# PHOTODIODE_CONT.net
KiCad netlist of a schematic drawn in Altium Designer
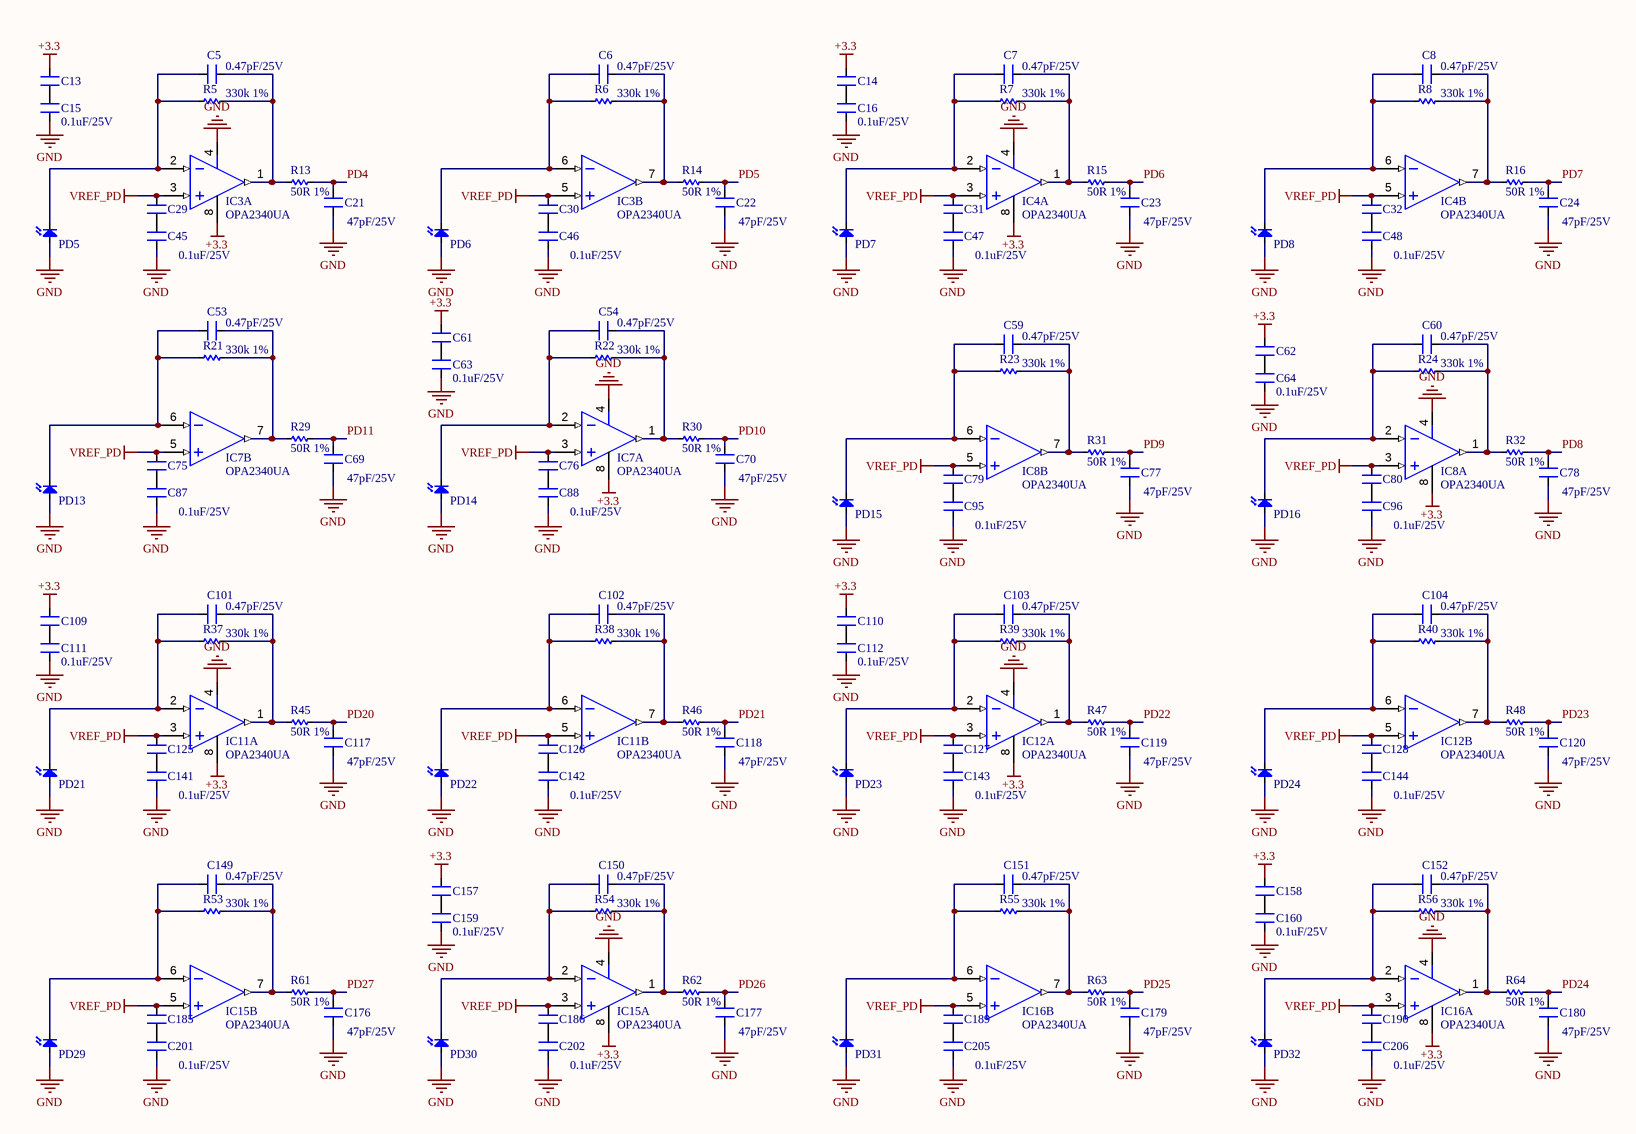
[diagram p0: PHOTODIODE (CONT).SchDoc]

(export (version "E")
  (design (tool "Eeschema 10.0.6"))
  (components
    (comp (ref "C5")
      (value "0.47pF/25V")
      (footprint "SM-0603")
      (description "0603")
      (libsource (lib "Capacitors") (part "CM"))
    )
    (comp (ref "C6")
      (value "0.47pF/25V")
      (footprint "SM-0603")
      (description "0603")
      (libsource (lib "Capacitors") (part "CM"))
    )
    (comp (ref "C7")
      (value "0.47pF/25V")
      (footprint "SM-0603")
      (description "0603")
      (libsource (lib "Capacitors") (part "CM"))
    )
    (comp (ref "C8")
      (value "0.47pF/25V")
      (footprint "SM-0603")
      (description "0603")
      (libsource (lib "Capacitors") (part "CM"))
    )
    (comp (ref "C13")
      (value "0.1uF/25V")
      (footprint "SM-0603")
      (description "0603")
      (libsource (lib "Capacitors") (part "CM"))
    )
    (comp (ref "C14")
      (value "0.1uF/25V")
      (footprint "SM-0603")
      (description "0603")
      (libsource (lib "Capacitors") (part "CM"))
    )
    (comp (ref "C15")
      (value "0.1uF/25V")
      (footprint "SM-0603")
      (description "0603")
      (libsource (lib "Capacitors") (part "CM"))
    )
    (comp (ref "C16")
      (value "0.1uF/25V")
      (footprint "SM-0603")
      (description "0603")
      (libsource (lib "Capacitors") (part "CM"))
    )
    (comp (ref "C21")
      (value "47pF/25V")
      (footprint "SM-0603")
      (description "0603")
      (libsource (lib "Capacitors") (part "CM"))
    )
    (comp (ref "C22")
      (value "47pF/25V")
      (footprint "SM-0603")
      (description "0603")
      (libsource (lib "Capacitors") (part "CM"))
    )
    (comp (ref "C23")
      (value "47pF/25V")
      (footprint "SM-0603")
      (description "0603")
      (libsource (lib "Capacitors") (part "CM"))
    )
    (comp (ref "C24")
      (value "47pF/25V")
      (footprint "SM-0603")
      (description "0603")
      (libsource (lib "Capacitors") (part "CM"))
    )
    (comp (ref "C29")
      (value "0.1uF/25V")
      (footprint "SM-0603")
      (description "0603")
      (libsource (lib "Capacitors") (part "CM"))
    )
    (comp (ref "C30")
      (value "0.1uF/25V")
      (footprint "SM-0603")
      (description "0603")
      (libsource (lib "Capacitors") (part "CM"))
    )
    (comp (ref "C31")
      (value "0.1uF/25V")
      (footprint "SM-0603")
      (description "0603")
      (libsource (lib "Capacitors") (part "CM"))
    )
    (comp (ref "C32")
      (value "0.1uF/25V")
      (footprint "SM-0603")
      (description "0603")
      (libsource (lib "Capacitors") (part "CM"))
    )
    (comp (ref "C45")
      (value "0.1uF/25V")
      (footprint "SM-0603")
      (description "0603")
      (libsource (lib "Capacitors") (part "CM"))
    )
    (comp (ref "C46")
      (value "0.1uF/25V")
      (footprint "SM-0603")
      (description "0603")
      (libsource (lib "Capacitors") (part "CM"))
    )
    (comp (ref "C47")
      (value "0.1uF/25V")
      (footprint "SM-0603")
      (description "0603")
      (libsource (lib "Capacitors") (part "CM"))
    )
    (comp (ref "C48")
      (value "0.1uF/25V")
      (footprint "SM-0603")
      (description "0603")
      (libsource (lib "Capacitors") (part "CM"))
    )
    (comp (ref "C53")
      (value "0.47pF/25V")
      (footprint "SM-0603")
      (description "0603")
      (libsource (lib "Capacitors") (part "CM"))
    )
    (comp (ref "C54")
      (value "0.47pF/25V")
      (footprint "SM-0603")
      (description "0603")
      (libsource (lib "Capacitors") (part "CM"))
    )
    (comp (ref "C59")
      (value "0.47pF/25V")
      (footprint "SM-0603")
      (description "0603")
      (libsource (lib "Capacitors") (part "CM"))
    )
    (comp (ref "C60")
      (value "0.47pF/25V")
      (footprint "SM-0603")
      (description "0603")
      (libsource (lib "Capacitors") (part "CM"))
    )
    (comp (ref "C61")
      (value "0.1uF/25V")
      (footprint "SM-0603")
      (description "0603")
      (libsource (lib "Capacitors") (part "CM"))
    )
    (comp (ref "C62")
      (value "0.1uF/25V")
      (footprint "SM-0603")
      (description "0603")
      (libsource (lib "Capacitors") (part "CM"))
    )
    (comp (ref "C63")
      (value "0.1uF/25V")
      (footprint "SM-0603")
      (description "0603")
      (libsource (lib "Capacitors") (part "CM"))
    )
    (comp (ref "C64")
      (value "0.1uF/25V")
      (footprint "SM-0603")
      (description "0603")
      (libsource (lib "Capacitors") (part "CM"))
    )
    (comp (ref "C69")
      (value "47pF/25V")
      (footprint "SM-0603")
      (description "0603")
      (libsource (lib "Capacitors") (part "CM"))
    )
    (comp (ref "C70")
      (value "47pF/25V")
      (footprint "SM-0603")
      (description "0603")
      (libsource (lib "Capacitors") (part "CM"))
    )
    (comp (ref "C75")
      (value "0.1uF/25V")
      (footprint "SM-0603")
      (description "0603")
      (libsource (lib "Capacitors") (part "CM"))
    )
    (comp (ref "C76")
      (value "0.1uF/25V")
      (footprint "SM-0603")
      (description "0603")
      (libsource (lib "Capacitors") (part "CM"))
    )
    (comp (ref "C77")
      (value "47pF/25V")
      (footprint "SM-0603")
      (description "0603")
      (libsource (lib "Capacitors") (part "CM"))
    )
    (comp (ref "C78")
      (value "47pF/25V")
      (footprint "SM-0603")
      (description "0603")
      (libsource (lib "Capacitors") (part "CM"))
    )
    (comp (ref "C79")
      (value "0.1uF/25V")
      (footprint "SM-0603")
      (description "0603")
      (libsource (lib "Capacitors") (part "CM"))
    )
    (comp (ref "C80")
      (value "0.1uF/25V")
      (footprint "SM-0603")
      (description "0603")
      (libsource (lib "Capacitors") (part "CM"))
    )
    (comp (ref "C87")
      (value "0.1uF/25V")
      (footprint "SM-0603")
      (description "0603")
      (libsource (lib "Capacitors") (part "CM"))
    )
    (comp (ref "C88")
      (value "0.1uF/25V")
      (footprint "SM-0603")
      (description "0603")
      (libsource (lib "Capacitors") (part "CM"))
    )
    (comp (ref "C95")
      (value "0.1uF/25V")
      (footprint "SM-0603")
      (description "0603")
      (libsource (lib "Capacitors") (part "CM"))
    )
    (comp (ref "C96")
      (value "0.1uF/25V")
      (footprint "SM-0603")
      (description "0603")
      (libsource (lib "Capacitors") (part "CM"))
    )
    (comp (ref "C101")
      (value "0.47pF/25V")
      (footprint "SM-0603")
      (description "0603")
      (libsource (lib "Capacitors") (part "CM"))
    )
    (comp (ref "C102")
      (value "0.47pF/25V")
      (footprint "SM-0603")
      (description "0603")
      (libsource (lib "Capacitors") (part "CM"))
    )
    (comp (ref "C103")
      (value "0.47pF/25V")
      (footprint "SM-0603")
      (description "0603")
      (libsource (lib "Capacitors") (part "CM"))
    )
    (comp (ref "C104")
      (value "0.47pF/25V")
      (footprint "SM-0603")
      (description "0603")
      (libsource (lib "Capacitors") (part "CM"))
    )
    (comp (ref "C109")
      (value "0.1uF/25V")
      (footprint "SM-0603")
      (description "0603")
      (libsource (lib "Capacitors") (part "CM"))
    )
    (comp (ref "C110")
      (value "0.1uF/25V")
      (footprint "SM-0603")
      (description "0603")
      (libsource (lib "Capacitors") (part "CM"))
    )
    (comp (ref "C111")
      (value "0.1uF/25V")
      (footprint "SM-0603")
      (description "0603")
      (libsource (lib "Capacitors") (part "CM"))
    )
    (comp (ref "C112")
      (value "0.1uF/25V")
      (footprint "SM-0603")
      (description "0603")
      (libsource (lib "Capacitors") (part "CM"))
    )
    (comp (ref "C117")
      (value "47pF/25V")
      (footprint "SM-0603")
      (description "0603")
      (libsource (lib "Capacitors") (part "CM"))
    )
    (comp (ref "C118")
      (value "47pF/25V")
      (footprint "SM-0603")
      (description "0603")
      (libsource (lib "Capacitors") (part "CM"))
    )
    (comp (ref "C119")
      (value "47pF/25V")
      (footprint "SM-0603")
      (description "0603")
      (libsource (lib "Capacitors") (part "CM"))
    )
    (comp (ref "C120")
      (value "47pF/25V")
      (footprint "SM-0603")
      (description "0603")
      (libsource (lib "Capacitors") (part "CM"))
    )
    (comp (ref "C125")
      (value "0.1uF/25V")
      (footprint "SM-0603")
      (description "0603")
      (libsource (lib "Capacitors") (part "CM"))
    )
    (comp (ref "C126")
      (value "0.1uF/25V")
      (footprint "SM-0603")
      (description "0603")
      (libsource (lib "Capacitors") (part "CM"))
    )
    (comp (ref "C127")
      (value "0.1uF/25V")
      (footprint "SM-0603")
      (description "0603")
      (libsource (lib "Capacitors") (part "CM"))
    )
    (comp (ref "C128")
      (value "0.1uF/25V")
      (footprint "SM-0603")
      (description "0603")
      (libsource (lib "Capacitors") (part "CM"))
    )
    (comp (ref "C141")
      (value "0.1uF/25V")
      (footprint "SM-0603")
      (description "0603")
      (libsource (lib "Capacitors") (part "CM"))
    )
    (comp (ref "C142")
      (value "0.1uF/25V")
      (footprint "SM-0603")
      (description "0603")
      (libsource (lib "Capacitors") (part "CM"))
    )
    (comp (ref "C143")
      (value "0.1uF/25V")
      (footprint "SM-0603")
      (description "0603")
      (libsource (lib "Capacitors") (part "CM"))
    )
    (comp (ref "C144")
      (value "0.1uF/25V")
      (footprint "SM-0603")
      (description "0603")
      (libsource (lib "Capacitors") (part "CM"))
    )
    (comp (ref "C149")
      (value "0.47pF/25V")
      (footprint "SM-0603")
      (description "0603")
      (libsource (lib "Capacitors") (part "CM"))
    )
    (comp (ref "C150")
      (value "0.47pF/25V")
      (footprint "SM-0603")
      (description "0603")
      (libsource (lib "Capacitors") (part "CM"))
    )
    (comp (ref "C151")
      (value "0.47pF/25V")
      (footprint "SM-0603")
      (description "0603")
      (libsource (lib "Capacitors") (part "CM"))
    )
    (comp (ref "C152")
      (value "0.47pF/25V")
      (footprint "SM-0603")
      (description "0603")
      (libsource (lib "Capacitors") (part "CM"))
    )
    (comp (ref "C157")
      (value "0.1uF/25V")
      (footprint "SM-0603")
      (description "0603")
      (libsource (lib "Capacitors") (part "CM"))
    )
    (comp (ref "C158")
      (value "0.1uF/25V")
      (footprint "SM-0603")
      (description "0603")
      (libsource (lib "Capacitors") (part "CM"))
    )
    (comp (ref "C159")
      (value "0.1uF/25V")
      (footprint "SM-0603")
      (description "0603")
      (libsource (lib "Capacitors") (part "CM"))
    )
    (comp (ref "C160")
      (value "0.1uF/25V")
      (footprint "SM-0603")
      (description "0603")
      (libsource (lib "Capacitors") (part "CM"))
    )
    (comp (ref "C176")
      (value "47pF/25V")
      (footprint "SM-0603")
      (description "0603")
      (libsource (lib "Capacitors") (part "CM"))
    )
    (comp (ref "C177")
      (value "47pF/25V")
      (footprint "SM-0603")
      (description "0603")
      (libsource (lib "Capacitors") (part "CM"))
    )
    (comp (ref "C179")
      (value "47pF/25V")
      (footprint "SM-0603")
      (description "0603")
      (libsource (lib "Capacitors") (part "CM"))
    )
    (comp (ref "C180")
      (value "47pF/25V")
      (footprint "SM-0603")
      (description "0603")
      (libsource (lib "Capacitors") (part "CM"))
    )
    (comp (ref "C185")
      (value "0.1uF/25V")
      (footprint "SM-0603")
      (description "0603")
      (libsource (lib "Capacitors") (part "CM"))
    )
    (comp (ref "C186")
      (value "0.1uF/25V")
      (footprint "SM-0603")
      (description "0603")
      (libsource (lib "Capacitors") (part "CM"))
    )
    (comp (ref "C189")
      (value "0.1uF/25V")
      (footprint "SM-0603")
      (description "0603")
      (libsource (lib "Capacitors") (part "CM"))
    )
    (comp (ref "C190")
      (value "0.1uF/25V")
      (footprint "SM-0603")
      (description "0603")
      (libsource (lib "Capacitors") (part "CM"))
    )
    (comp (ref "C201")
      (value "0.1uF/25V")
      (footprint "SM-0603")
      (description "0603")
      (libsource (lib "Capacitors") (part "CM"))
    )
    (comp (ref "C202")
      (value "0.1uF/25V")
      (footprint "SM-0603")
      (description "0603")
      (libsource (lib "Capacitors") (part "CM"))
    )
    (comp (ref "C205")
      (value "0.1uF/25V")
      (footprint "SM-0603")
      (description "0603")
      (libsource (lib "Capacitors") (part "CM"))
    )
    (comp (ref "C206")
      (value "0.1uF/25V")
      (footprint "SM-0603")
      (description "0603")
      (libsource (lib "Capacitors") (part "CM"))
    )
    (comp (ref "IC3")
      (value "OPA2340UA")
      (footprint "SO8")
      (description "8SOIC")
      (libsource (lib "Library") (part "LM358"))
    )
    (comp (ref "IC4")
      (value "OPA2340UA")
      (footprint "SO8")
      (description "8SOIC")
      (libsource (lib "Library") (part "LM358"))
    )
    (comp (ref "IC7")
      (value "OPA2340UA")
      (footprint "SO8")
      (description "8SOIC")
      (libsource (lib "Library") (part "LM358"))
    )
    (comp (ref "IC8")
      (value "OPA2340UA")
      (footprint "SO8")
      (description "8SOIC")
      (libsource (lib "Library") (part "LM358"))
    )
    (comp (ref "IC11")
      (value "OPA2340UA")
      (footprint "SO8")
      (description "8SOIC")
      (libsource (lib "Library") (part "LM358"))
    )
    (comp (ref "IC12")
      (value "OPA2340UA")
      (footprint "SO8")
      (description "8SOIC")
      (libsource (lib "Library") (part "LM358"))
    )
    (comp (ref "IC15")
      (value "OPA2340UA")
      (footprint "SO8")
      (description "8SOIC")
      (libsource (lib "Library") (part "LM358"))
    )
    (comp (ref "IC16")
      (value "OPA2340UA")
      (footprint "SO8")
      (description "8SOIC")
      (libsource (lib "Library") (part "LM358"))
    )
    (comp (ref "PD5")
      (value "Photodiode")
      (footprint "SFH2240")
      (libsource (lib "Library") (part "Photodiode"))
    )
    (comp (ref "PD6")
      (value "Photodiode")
      (footprint "SFH2240")
      (libsource (lib "Library") (part "Photodiode"))
    )
    (comp (ref "PD7")
      (value "Photodiode")
      (footprint "SFH2240")
      (libsource (lib "Library") (part "Photodiode"))
    )
    (comp (ref "PD8")
      (value "Photodiode")
      (footprint "SFH2240")
      (libsource (lib "Library") (part "Photodiode"))
    )
    (comp (ref "PD13")
      (value "Photodiode")
      (footprint "SFH2240")
      (libsource (lib "Library") (part "Photodiode"))
    )
    (comp (ref "PD14")
      (value "Photodiode")
      (footprint "SFH2240")
      (libsource (lib "Library") (part "Photodiode"))
    )
    (comp (ref "PD15")
      (value "Photodiode")
      (footprint "SFH2240")
      (libsource (lib "Library") (part "Photodiode"))
    )
    (comp (ref "PD16")
      (value "Photodiode")
      (footprint "SFH2240")
      (libsource (lib "Library") (part "Photodiode"))
    )
    (comp (ref "PD21")
      (value "Photodiode")
      (footprint "SFH2240")
      (libsource (lib "Library") (part "Photodiode"))
    )
    (comp (ref "PD22")
      (value "Photodiode")
      (footprint "SFH2240")
      (libsource (lib "Library") (part "Photodiode"))
    )
    (comp (ref "PD23")
      (value "Photodiode")
      (footprint "SFH2240")
      (libsource (lib "Library") (part "Photodiode"))
    )
    (comp (ref "PD24")
      (value "Photodiode")
      (footprint "SFH2240")
      (libsource (lib "Library") (part "Photodiode"))
    )
    (comp (ref "PD29")
      (value "Photodiode")
      (footprint "SFH2240")
      (libsource (lib "Library") (part "Photodiode"))
    )
    (comp (ref "PD30")
      (value "Photodiode")
      (footprint "SFH2240")
      (libsource (lib "Library") (part "Photodiode"))
    )
    (comp (ref "PD31")
      (value "Photodiode")
      (footprint "SFH2240")
      (libsource (lib "Library") (part "Photodiode"))
    )
    (comp (ref "PD32")
      (value "Photodiode")
      (footprint "SFH2240")
      (libsource (lib "Library") (part "Photodiode"))
    )
    (comp (ref "R5")
      (value "330k 1%")
      (footprint "RES-SMD-0603")
      (description "0603")
      (fields
        (field (name "MANUFACTURER") "Generic Components")
        (field (name "PUBLISHER") "Altium Hobart Technology Centre")
      )
      (libsource (lib "Library") (part "Res-SMD"))
    )
    (comp (ref "R6")
      (value "330k 1%")
      (footprint "RES-SMD-0603")
      (description "0603")
      (fields
        (field (name "MANUFACTURER") "Generic Components")
        (field (name "PUBLISHER") "Altium Hobart Technology Centre")
      )
      (libsource (lib "Library") (part "Res-SMD"))
    )
    (comp (ref "R7")
      (value "330k 1%")
      (footprint "RES-SMD-0603")
      (description "0603")
      (fields
        (field (name "MANUFACTURER") "Generic Components")
        (field (name "PUBLISHER") "Altium Hobart Technology Centre")
      )
      (libsource (lib "Library") (part "Res-SMD"))
    )
    (comp (ref "R8")
      (value "330k 1%")
      (footprint "RES-SMD-0603")
      (description "0603")
      (fields
        (field (name "MANUFACTURER") "Generic Components")
        (field (name "PUBLISHER") "Altium Hobart Technology Centre")
      )
      (libsource (lib "Library") (part "Res-SMD"))
    )
    (comp (ref "R13")
      (value "50R 1%")
      (footprint "RES-SMD-0603")
      (description "0603")
      (fields
        (field (name "MANUFACTURER") "Generic Components")
        (field (name "PUBLISHER") "Altium Hobart Technology Centre")
      )
      (libsource (lib "Library") (part "Res-SMD"))
    )
    (comp (ref "R14")
      (value "50R 1%")
      (footprint "RES-SMD-0603")
      (description "0603")
      (fields
        (field (name "MANUFACTURER") "Generic Components")
        (field (name "PUBLISHER") "Altium Hobart Technology Centre")
      )
      (libsource (lib "Library") (part "Res-SMD"))
    )
    (comp (ref "R15")
      (value "50R 1%")
      (footprint "RES-SMD-0603")
      (description "0603")
      (fields
        (field (name "MANUFACTURER") "Generic Components")
        (field (name "PUBLISHER") "Altium Hobart Technology Centre")
      )
      (libsource (lib "Library") (part "Res-SMD"))
    )
    (comp (ref "R16")
      (value "50R 1%")
      (footprint "RES-SMD-0603")
      (description "0603")
      (fields
        (field (name "MANUFACTURER") "Generic Components")
        (field (name "PUBLISHER") "Altium Hobart Technology Centre")
      )
      (libsource (lib "Library") (part "Res-SMD"))
    )
    (comp (ref "R21")
      (value "330k 1%")
      (footprint "RES-SMD-0603")
      (description "0603")
      (fields
        (field (name "MANUFACTURER") "Generic Components")
        (field (name "PUBLISHER") "Altium Hobart Technology Centre")
      )
      (libsource (lib "Library") (part "Res-SMD"))
    )
    (comp (ref "R22")
      (value "330k 1%")
      (footprint "RES-SMD-0603")
      (description "0603")
      (fields
        (field (name "MANUFACTURER") "Generic Components")
        (field (name "PUBLISHER") "Altium Hobart Technology Centre")
      )
      (libsource (lib "Library") (part "Res-SMD"))
    )
    (comp (ref "R23")
      (value "330k 1%")
      (footprint "RES-SMD-0603")
      (description "0603")
      (fields
        (field (name "MANUFACTURER") "Generic Components")
        (field (name "PUBLISHER") "Altium Hobart Technology Centre")
      )
      (libsource (lib "Library") (part "Res-SMD"))
    )
    (comp (ref "R24")
      (value "330k 1%")
      (footprint "RES-SMD-0603")
      (description "0603")
      (fields
        (field (name "MANUFACTURER") "Generic Components")
        (field (name "PUBLISHER") "Altium Hobart Technology Centre")
      )
      (libsource (lib "Library") (part "Res-SMD"))
    )
    (comp (ref "R29")
      (value "50R 1%")
      (footprint "RES-SMD-0603")
      (description "0603")
      (fields
        (field (name "MANUFACTURER") "Generic Components")
        (field (name "PUBLISHER") "Altium Hobart Technology Centre")
      )
      (libsource (lib "Library") (part "Res-SMD"))
    )
    (comp (ref "R30")
      (value "50R 1%")
      (footprint "RES-SMD-0603")
      (description "0603")
      (fields
        (field (name "MANUFACTURER") "Generic Components")
        (field (name "PUBLISHER") "Altium Hobart Technology Centre")
      )
      (libsource (lib "Library") (part "Res-SMD"))
    )
    (comp (ref "R31")
      (value "50R 1%")
      (footprint "RES-SMD-0603")
      (description "0603")
      (fields
        (field (name "MANUFACTURER") "Generic Components")
        (field (name "PUBLISHER") "Altium Hobart Technology Centre")
      )
      (libsource (lib "Library") (part "Res-SMD"))
    )
    (comp (ref "R32")
      (value "50R 1%")
      (footprint "RES-SMD-0603")
      (description "0603")
      (fields
        (field (name "MANUFACTURER") "Generic Components")
        (field (name "PUBLISHER") "Altium Hobart Technology Centre")
      )
      (libsource (lib "Library") (part "Res-SMD"))
    )
    (comp (ref "R37")
      (value "330k 1%")
      (footprint "RES-SMD-0603")
      (description "0603")
      (fields
        (field (name "MANUFACTURER") "Generic Components")
        (field (name "PUBLISHER") "Altium Hobart Technology Centre")
      )
      (libsource (lib "Library") (part "Res-SMD"))
    )
    (comp (ref "R38")
      (value "330k 1%")
      (footprint "RES-SMD-0603")
      (description "0603")
      (fields
        (field (name "MANUFACTURER") "Generic Components")
        (field (name "PUBLISHER") "Altium Hobart Technology Centre")
      )
      (libsource (lib "Library") (part "Res-SMD"))
    )
    (comp (ref "R39")
      (value "330k 1%")
      (footprint "RES-SMD-0603")
      (description "0603")
      (fields
        (field (name "MANUFACTURER") "Generic Components")
        (field (name "PUBLISHER") "Altium Hobart Technology Centre")
      )
      (libsource (lib "Library") (part "Res-SMD"))
    )
    (comp (ref "R40")
      (value "330k 1%")
      (footprint "RES-SMD-0603")
      (description "0603")
      (fields
        (field (name "MANUFACTURER") "Generic Components")
        (field (name "PUBLISHER") "Altium Hobart Technology Centre")
      )
      (libsource (lib "Library") (part "Res-SMD"))
    )
    (comp (ref "R45")
      (value "50R 1%")
      (footprint "RES-SMD-0603")
      (description "0603")
      (fields
        (field (name "MANUFACTURER") "Generic Components")
        (field (name "PUBLISHER") "Altium Hobart Technology Centre")
      )
      (libsource (lib "Library") (part "Res-SMD"))
    )
    (comp (ref "R46")
      (value "50R 1%")
      (footprint "RES-SMD-0603")
      (description "0603")
      (fields
        (field (name "MANUFACTURER") "Generic Components")
        (field (name "PUBLISHER") "Altium Hobart Technology Centre")
      )
      (libsource (lib "Library") (part "Res-SMD"))
    )
    (comp (ref "R47")
      (value "50R 1%")
      (footprint "RES-SMD-0603")
      (description "0603")
      (fields
        (field (name "MANUFACTURER") "Generic Components")
        (field (name "PUBLISHER") "Altium Hobart Technology Centre")
      )
      (libsource (lib "Library") (part "Res-SMD"))
    )
    (comp (ref "R48")
      (value "50R 1%")
      (footprint "RES-SMD-0603")
      (description "0603")
      (fields
        (field (name "MANUFACTURER") "Generic Components")
        (field (name "PUBLISHER") "Altium Hobart Technology Centre")
      )
      (libsource (lib "Library") (part "Res-SMD"))
    )
    (comp (ref "R53")
      (value "330k 1%")
      (footprint "RES-SMD-0603")
      (description "0603")
      (fields
        (field (name "MANUFACTURER") "Generic Components")
        (field (name "PUBLISHER") "Altium Hobart Technology Centre")
      )
      (libsource (lib "Library") (part "Res-SMD"))
    )
    (comp (ref "R54")
      (value "330k 1%")
      (footprint "RES-SMD-0603")
      (description "0603")
      (fields
        (field (name "MANUFACTURER") "Generic Components")
        (field (name "PUBLISHER") "Altium Hobart Technology Centre")
      )
      (libsource (lib "Library") (part "Res-SMD"))
    )
    (comp (ref "R55")
      (value "330k 1%")
      (footprint "RES-SMD-0603")
      (description "0603")
      (fields
        (field (name "MANUFACTURER") "Generic Components")
        (field (name "PUBLISHER") "Altium Hobart Technology Centre")
      )
      (libsource (lib "Library") (part "Res-SMD"))
    )
    (comp (ref "R56")
      (value "330k 1%")
      (footprint "RES-SMD-0603")
      (description "0603")
      (fields
        (field (name "MANUFACTURER") "Generic Components")
        (field (name "PUBLISHER") "Altium Hobart Technology Centre")
      )
      (libsource (lib "Library") (part "Res-SMD"))
    )
    (comp (ref "R61")
      (value "50R 1%")
      (footprint "RES-SMD-0603")
      (description "0603")
      (fields
        (field (name "MANUFACTURER") "Generic Components")
        (field (name "PUBLISHER") "Altium Hobart Technology Centre")
      )
      (libsource (lib "Library") (part "Res-SMD"))
    )
    (comp (ref "R62")
      (value "50R 1%")
      (footprint "RES-SMD-0603")
      (description "0603")
      (fields
        (field (name "MANUFACTURER") "Generic Components")
        (field (name "PUBLISHER") "Altium Hobart Technology Centre")
      )
      (libsource (lib "Library") (part "Res-SMD"))
    )
    (comp (ref "R63")
      (value "50R 1%")
      (footprint "RES-SMD-0603")
      (description "0603")
      (fields
        (field (name "MANUFACTURER") "Generic Components")
        (field (name "PUBLISHER") "Altium Hobart Technology Centre")
      )
      (libsource (lib "Library") (part "Res-SMD"))
    )
    (comp (ref "R64")
      (value "50R 1%")
      (footprint "RES-SMD-0603")
      (description "0603")
      (fields
        (field (name "MANUFACTURER") "Generic Components")
        (field (name "PUBLISHER") "Altium Hobart Technology Centre")
      )
      (libsource (lib "Library") (part "Res-SMD"))
    )
  )
  (nets
    (net (code "1") (name "+3.3") (class "Default")
      (node (ref "C109") (pin "2") (pinfunction "2_2") (pintype "passive"))
      (node (ref "C110") (pin "2") (pinfunction "2_2") (pintype "passive"))
      (node (ref "C13") (pin "2") (pinfunction "2_2") (pintype "passive"))
      (node (ref "C14") (pin "2") (pinfunction "2_2") (pintype "passive"))
      (node (ref "C157") (pin "2") (pinfunction "2_2") (pintype "passive"))
      (node (ref "C158") (pin "2") (pinfunction "2_2") (pintype "passive"))
      (node (ref "C61") (pin "2") (pinfunction "2_2") (pintype "passive"))
      (node (ref "C62") (pin "2") (pinfunction "2_2") (pintype "passive"))
      (node (ref "IC11") (pin "8") (pinfunction "+V_8") (pintype "passive"))
      (node (ref "IC12") (pin "8") (pinfunction "+V_8") (pintype "passive"))
      (node (ref "IC15") (pin "8") (pinfunction "+V_8") (pintype "passive"))
      (node (ref "IC16") (pin "8") (pinfunction "+V_8") (pintype "passive"))
      (node (ref "IC3") (pin "8") (pinfunction "+V_8") (pintype "passive"))
      (node (ref "IC4") (pin "8") (pinfunction "+V_8") (pintype "passive"))
      (node (ref "IC7") (pin "8") (pinfunction "+V_8") (pintype "passive"))
      (node (ref "IC8") (pin "8") (pinfunction "+V_8") (pintype "passive"))
    )
    (net (code "2") (name "/PD4") (class "Default")
      (node (ref "C21") (pin "2") (pinfunction "2_2") (pintype "passive"))
      (node (ref "R13") (pin "2") (pinfunction "2_2") (pintype "passive"))
    )
    (net (code "3") (name "/PD5") (class "Default")
      (node (ref "C22") (pin "2") (pinfunction "2_2") (pintype "passive"))
      (node (ref "R14") (pin "2") (pinfunction "2_2") (pintype "passive"))
    )
    (net (code "4") (name "/PD6") (class "Default")
      (node (ref "C23") (pin "2") (pinfunction "2_2") (pintype "passive"))
      (node (ref "R15") (pin "2") (pinfunction "2_2") (pintype "passive"))
    )
    (net (code "5") (name "/PD7") (class "Default")
      (node (ref "C24") (pin "2") (pinfunction "2_2") (pintype "passive"))
      (node (ref "R16") (pin "2") (pinfunction "2_2") (pintype "passive"))
    )
    (net (code "6") (name "/PD8") (class "Default")
      (node (ref "C78") (pin "2") (pinfunction "2_2") (pintype "passive"))
      (node (ref "R32") (pin "2") (pinfunction "2_2") (pintype "passive"))
    )
    (net (code "7") (name "/PD9") (class "Default")
      (node (ref "C77") (pin "2") (pinfunction "2_2") (pintype "passive"))
      (node (ref "R31") (pin "2") (pinfunction "2_2") (pintype "passive"))
    )
    (net (code "8") (name "/PD10") (class "Default")
      (node (ref "C70") (pin "2") (pinfunction "2_2") (pintype "passive"))
      (node (ref "R30") (pin "2") (pinfunction "2_2") (pintype "passive"))
    )
    (net (code "9") (name "/PD11") (class "Default")
      (node (ref "C69") (pin "2") (pinfunction "2_2") (pintype "passive"))
      (node (ref "R29") (pin "2") (pinfunction "2_2") (pintype "passive"))
    )
    (net (code "10") (name "/PD20") (class "Default")
      (node (ref "C117") (pin "2") (pinfunction "2_2") (pintype "passive"))
      (node (ref "R45") (pin "2") (pinfunction "2_2") (pintype "passive"))
    )
    (net (code "11") (name "/PD21") (class "Default")
      (node (ref "C118") (pin "2") (pinfunction "2_2") (pintype "passive"))
      (node (ref "R46") (pin "2") (pinfunction "2_2") (pintype "passive"))
    )
    (net (code "12") (name "/PD22") (class "Default")
      (node (ref "C119") (pin "2") (pinfunction "2_2") (pintype "passive"))
      (node (ref "R47") (pin "2") (pinfunction "2_2") (pintype "passive"))
    )
    (net (code "13") (name "/PD23") (class "Default")
      (node (ref "C120") (pin "2") (pinfunction "2_2") (pintype "passive"))
      (node (ref "R48") (pin "2") (pinfunction "2_2") (pintype "passive"))
    )
    (net (code "14") (name "/PD24") (class "Default")
      (node (ref "C180") (pin "2") (pinfunction "2_2") (pintype "passive"))
      (node (ref "R64") (pin "2") (pinfunction "2_2") (pintype "passive"))
    )
    (net (code "15") (name "/PD25") (class "Default")
      (node (ref "C179") (pin "2") (pinfunction "2_2") (pintype "passive"))
      (node (ref "R63") (pin "2") (pinfunction "2_2") (pintype "passive"))
    )
    (net (code "16") (name "/PD26") (class "Default")
      (node (ref "C177") (pin "2") (pinfunction "2_2") (pintype "passive"))
      (node (ref "R62") (pin "2") (pinfunction "2_2") (pintype "passive"))
    )
    (net (code "17") (name "/PD27") (class "Default")
      (node (ref "C176") (pin "2") (pinfunction "2_2") (pintype "passive"))
      (node (ref "R61") (pin "2") (pinfunction "2_2") (pintype "passive"))
    )
    (net (code "18") (name "GND") (class "Default")
      (node (ref "C111") (pin "1") (pinfunction "1_1") (pintype "passive"))
      (node (ref "C112") (pin "1") (pinfunction "1_1") (pintype "passive"))
      (node (ref "C117") (pin "1") (pinfunction "1_1") (pintype "passive"))
      (node (ref "C118") (pin "1") (pinfunction "1_1") (pintype "passive"))
      (node (ref "C119") (pin "1") (pinfunction "1_1") (pintype "passive"))
      (node (ref "C120") (pin "1") (pinfunction "1_1") (pintype "passive"))
      (node (ref "C141") (pin "1") (pinfunction "1_1") (pintype "passive"))
      (node (ref "C142") (pin "1") (pinfunction "1_1") (pintype "passive"))
      (node (ref "C143") (pin "1") (pinfunction "1_1") (pintype "passive"))
      (node (ref "C144") (pin "1") (pinfunction "1_1") (pintype "passive"))
      (node (ref "C15") (pin "1") (pinfunction "1_1") (pintype "passive"))
      (node (ref "C159") (pin "1") (pinfunction "1_1") (pintype "passive"))
      (node (ref "C16") (pin "1") (pinfunction "1_1") (pintype "passive"))
      (node (ref "C160") (pin "1") (pinfunction "1_1") (pintype "passive"))
      (node (ref "C176") (pin "1") (pinfunction "1_1") (pintype "passive"))
      (node (ref "C177") (pin "1") (pinfunction "1_1") (pintype "passive"))
      (node (ref "C179") (pin "1") (pinfunction "1_1") (pintype "passive"))
      (node (ref "C180") (pin "1") (pinfunction "1_1") (pintype "passive"))
      (node (ref "C201") (pin "1") (pinfunction "1_1") (pintype "passive"))
      (node (ref "C202") (pin "1") (pinfunction "1_1") (pintype "passive"))
      (node (ref "C205") (pin "1") (pinfunction "1_1") (pintype "passive"))
      (node (ref "C206") (pin "1") (pinfunction "1_1") (pintype "passive"))
      (node (ref "C21") (pin "1") (pinfunction "1_1") (pintype "passive"))
      (node (ref "C22") (pin "1") (pinfunction "1_1") (pintype "passive"))
      (node (ref "C23") (pin "1") (pinfunction "1_1") (pintype "passive"))
      (node (ref "C24") (pin "1") (pinfunction "1_1") (pintype "passive"))
      (node (ref "C45") (pin "1") (pinfunction "1_1") (pintype "passive"))
      (node (ref "C46") (pin "1") (pinfunction "1_1") (pintype "passive"))
      (node (ref "C47") (pin "1") (pinfunction "1_1") (pintype "passive"))
      (node (ref "C48") (pin "1") (pinfunction "1_1") (pintype "passive"))
      (node (ref "C63") (pin "1") (pinfunction "1_1") (pintype "passive"))
      (node (ref "C64") (pin "1") (pinfunction "1_1") (pintype "passive"))
      (node (ref "C69") (pin "1") (pinfunction "1_1") (pintype "passive"))
      (node (ref "C70") (pin "1") (pinfunction "1_1") (pintype "passive"))
      (node (ref "C77") (pin "1") (pinfunction "1_1") (pintype "passive"))
      (node (ref "C78") (pin "1") (pinfunction "1_1") (pintype "passive"))
      (node (ref "C87") (pin "1") (pinfunction "1_1") (pintype "passive"))
      (node (ref "C88") (pin "1") (pinfunction "1_1") (pintype "passive"))
      (node (ref "C95") (pin "1") (pinfunction "1_1") (pintype "passive"))
      (node (ref "C96") (pin "1") (pinfunction "1_1") (pintype "passive"))
      (node (ref "IC11") (pin "4") (pinfunction "-V_4") (pintype "passive"))
      (node (ref "IC12") (pin "4") (pinfunction "-V_4") (pintype "passive"))
      (node (ref "IC15") (pin "4") (pinfunction "-V_4") (pintype "passive"))
      (node (ref "IC16") (pin "4") (pinfunction "-V_4") (pintype "passive"))
      (node (ref "IC3") (pin "4") (pinfunction "-V_4") (pintype "passive"))
      (node (ref "IC4") (pin "4") (pinfunction "-V_4") (pintype "passive"))
      (node (ref "IC7") (pin "4") (pinfunction "-V_4") (pintype "passive"))
      (node (ref "IC8") (pin "4") (pinfunction "-V_4") (pintype "passive"))
      (node (ref "PD13") (pin "1") (pinfunction "A_1") (pintype "passive"))
      (node (ref "PD14") (pin "1") (pinfunction "A_1") (pintype "passive"))
      (node (ref "PD15") (pin "1") (pinfunction "A_1") (pintype "passive"))
      (node (ref "PD16") (pin "1") (pinfunction "A_1") (pintype "passive"))
      (node (ref "PD21") (pin "1") (pinfunction "A_1") (pintype "passive"))
      (node (ref "PD22") (pin "1") (pinfunction "A_1") (pintype "passive"))
      (node (ref "PD23") (pin "1") (pinfunction "A_1") (pintype "passive"))
      (node (ref "PD24") (pin "1") (pinfunction "A_1") (pintype "passive"))
      (node (ref "PD29") (pin "1") (pinfunction "A_1") (pintype "passive"))
      (node (ref "PD30") (pin "1") (pinfunction "A_1") (pintype "passive"))
      (node (ref "PD31") (pin "1") (pinfunction "A_1") (pintype "passive"))
      (node (ref "PD32") (pin "1") (pinfunction "A_1") (pintype "passive"))
      (node (ref "PD5") (pin "1") (pinfunction "A_1") (pintype "passive"))
      (node (ref "PD6") (pin "1") (pinfunction "A_1") (pintype "passive"))
      (node (ref "PD7") (pin "1") (pinfunction "A_1") (pintype "passive"))
      (node (ref "PD8") (pin "1") (pinfunction "A_1") (pintype "passive"))
    )
    (net (code "19") (name "Net-(C13-Pad1)") (class "Default")
      (node (ref "C13") (pin "1") (pinfunction "1_1") (pintype "passive"))
      (node (ref "C15") (pin "2") (pinfunction "2_2") (pintype "passive"))
    )
    (net (code "20") (name "Net-(C14-Pad1)") (class "Default")
      (node (ref "C14") (pin "1") (pinfunction "1_1") (pintype "passive"))
      (node (ref "C16") (pin "2") (pinfunction "2_2") (pintype "passive"))
    )
    (net (code "21") (name "Net-(C29-Pad1)") (class "Default")
      (node (ref "C29") (pin "1") (pinfunction "1_1") (pintype "passive"))
      (node (ref "C45") (pin "2") (pinfunction "2_2") (pintype "passive"))
    )
    (net (code "22") (name "Net-(C30-Pad1)") (class "Default")
      (node (ref "C30") (pin "1") (pinfunction "1_1") (pintype "passive"))
      (node (ref "C46") (pin "2") (pinfunction "2_2") (pintype "passive"))
    )
    (net (code "23") (name "Net-(C31-Pad1)") (class "Default")
      (node (ref "C31") (pin "1") (pinfunction "1_1") (pintype "passive"))
      (node (ref "C47") (pin "2") (pinfunction "2_2") (pintype "passive"))
    )
    (net (code "24") (name "Net-(C32-Pad1)") (class "Default")
      (node (ref "C32") (pin "1") (pinfunction "1_1") (pintype "passive"))
      (node (ref "C48") (pin "2") (pinfunction "2_2") (pintype "passive"))
    )
    (net (code "25") (name "Net-(C61-Pad1)") (class "Default")
      (node (ref "C61") (pin "1") (pinfunction "1_1") (pintype "passive"))
      (node (ref "C63") (pin "2") (pinfunction "2_2") (pintype "passive"))
    )
    (net (code "26") (name "Net-(C62-Pad1)") (class "Default")
      (node (ref "C62") (pin "1") (pinfunction "1_1") (pintype "passive"))
      (node (ref "C64") (pin "2") (pinfunction "2_2") (pintype "passive"))
    )
    (net (code "27") (name "Net-(C75-Pad1)") (class "Default")
      (node (ref "C75") (pin "1") (pinfunction "1_1") (pintype "passive"))
      (node (ref "C87") (pin "2") (pinfunction "2_2") (pintype "passive"))
    )
    (net (code "28") (name "Net-(C76-Pad1)") (class "Default")
      (node (ref "C76") (pin "1") (pinfunction "1_1") (pintype "passive"))
      (node (ref "C88") (pin "2") (pinfunction "2_2") (pintype "passive"))
    )
    (net (code "29") (name "Net-(C79-Pad1)") (class "Default")
      (node (ref "C79") (pin "1") (pinfunction "1_1") (pintype "passive"))
      (node (ref "C95") (pin "2") (pinfunction "2_2") (pintype "passive"))
    )
    (net (code "30") (name "Net-(C80-Pad1)") (class "Default")
      (node (ref "C80") (pin "1") (pinfunction "1_1") (pintype "passive"))
      (node (ref "C96") (pin "2") (pinfunction "2_2") (pintype "passive"))
    )
    (net (code "31") (name "Net-(C109-Pad1)") (class "Default")
      (node (ref "C109") (pin "1") (pinfunction "1_1") (pintype "passive"))
      (node (ref "C111") (pin "2") (pinfunction "2_2") (pintype "passive"))
    )
    (net (code "32") (name "Net-(C110-Pad1)") (class "Default")
      (node (ref "C110") (pin "1") (pinfunction "1_1") (pintype "passive"))
      (node (ref "C112") (pin "2") (pinfunction "2_2") (pintype "passive"))
    )
    (net (code "33") (name "Net-(C125-Pad1)") (class "Default")
      (node (ref "C125") (pin "1") (pinfunction "1_1") (pintype "passive"))
      (node (ref "C141") (pin "2") (pinfunction "2_2") (pintype "passive"))
    )
    (net (code "34") (name "Net-(C126-Pad1)") (class "Default")
      (node (ref "C126") (pin "1") (pinfunction "1_1") (pintype "passive"))
      (node (ref "C142") (pin "2") (pinfunction "2_2") (pintype "passive"))
    )
    (net (code "35") (name "Net-(C127-Pad1)") (class "Default")
      (node (ref "C127") (pin "1") (pinfunction "1_1") (pintype "passive"))
      (node (ref "C143") (pin "2") (pinfunction "2_2") (pintype "passive"))
    )
    (net (code "36") (name "Net-(C128-Pad1)") (class "Default")
      (node (ref "C128") (pin "1") (pinfunction "1_1") (pintype "passive"))
      (node (ref "C144") (pin "2") (pinfunction "2_2") (pintype "passive"))
    )
    (net (code "37") (name "Net-(C157-Pad1)") (class "Default")
      (node (ref "C157") (pin "1") (pinfunction "1_1") (pintype "passive"))
      (node (ref "C159") (pin "2") (pinfunction "2_2") (pintype "passive"))
    )
    (net (code "38") (name "Net-(C158-Pad1)") (class "Default")
      (node (ref "C158") (pin "1") (pinfunction "1_1") (pintype "passive"))
      (node (ref "C160") (pin "2") (pinfunction "2_2") (pintype "passive"))
    )
    (net (code "39") (name "Net-(C185-Pad1)") (class "Default")
      (node (ref "C185") (pin "1") (pinfunction "1_1") (pintype "passive"))
      (node (ref "C201") (pin "2") (pinfunction "2_2") (pintype "passive"))
    )
    (net (code "40") (name "Net-(C186-Pad1)") (class "Default")
      (node (ref "C186") (pin "1") (pinfunction "1_1") (pintype "passive"))
      (node (ref "C202") (pin "2") (pinfunction "2_2") (pintype "passive"))
    )
    (net (code "41") (name "Net-(C189-Pad1)") (class "Default")
      (node (ref "C189") (pin "1") (pinfunction "1_1") (pintype "passive"))
      (node (ref "C205") (pin "2") (pinfunction "2_2") (pintype "passive"))
    )
    (net (code "42") (name "Net-(C190-Pad1)") (class "Default")
      (node (ref "C190") (pin "1") (pinfunction "1_1") (pintype "passive"))
      (node (ref "C206") (pin "2") (pinfunction "2_2") (pintype "passive"))
    )
    (net (code "43") (name "Net-(IC3A-IN-)") (class "Default")
      (node (ref "C5") (pin "1") (pinfunction "1_1") (pintype "passive"))
      (node (ref "IC3") (pin "2") (pinfunction "IN-_2") (pintype "input"))
      (node (ref "PD5") (pin "2") (pinfunction "K_2") (pintype "passive"))
      (node (ref "R5") (pin "1") (pinfunction "1_1") (pintype "passive"))
    )
    (net (code "44") (name "Net-(IC3A-OUT)") (class "Default")
      (node (ref "C5") (pin "2") (pinfunction "2_2") (pintype "passive"))
      (node (ref "IC3") (pin "1") (pinfunction "OUT_1") (pintype "output"))
      (node (ref "R13") (pin "1") (pinfunction "1_1") (pintype "passive"))
      (node (ref "R5") (pin "2") (pinfunction "2_2") (pintype "passive"))
    )
    (net (code "45") (name "Net-(IC3B-IN-)") (class "Default")
      (node (ref "C6") (pin "1") (pinfunction "1_1") (pintype "passive"))
      (node (ref "IC3") (pin "6") (pinfunction "IN-_6") (pintype "input"))
      (node (ref "PD6") (pin "2") (pinfunction "K_2") (pintype "passive"))
      (node (ref "R6") (pin "1") (pinfunction "1_1") (pintype "passive"))
    )
    (net (code "46") (name "Net-(IC3B-OUT)") (class "Default")
      (node (ref "C6") (pin "2") (pinfunction "2_2") (pintype "passive"))
      (node (ref "IC3") (pin "7") (pinfunction "OUT_7") (pintype "output"))
      (node (ref "R14") (pin "1") (pinfunction "1_1") (pintype "passive"))
      (node (ref "R6") (pin "2") (pinfunction "2_2") (pintype "passive"))
    )
    (net (code "47") (name "Net-(IC4A-IN-)") (class "Default")
      (node (ref "C7") (pin "1") (pinfunction "1_1") (pintype "passive"))
      (node (ref "IC4") (pin "2") (pinfunction "IN-_2") (pintype "input"))
      (node (ref "PD7") (pin "2") (pinfunction "K_2") (pintype "passive"))
      (node (ref "R7") (pin "1") (pinfunction "1_1") (pintype "passive"))
    )
    (net (code "48") (name "Net-(IC4A-OUT)") (class "Default")
      (node (ref "C7") (pin "2") (pinfunction "2_2") (pintype "passive"))
      (node (ref "IC4") (pin "1") (pinfunction "OUT_1") (pintype "output"))
      (node (ref "R15") (pin "1") (pinfunction "1_1") (pintype "passive"))
      (node (ref "R7") (pin "2") (pinfunction "2_2") (pintype "passive"))
    )
    (net (code "49") (name "Net-(IC4B-IN-)") (class "Default")
      (node (ref "C8") (pin "1") (pinfunction "1_1") (pintype "passive"))
      (node (ref "IC4") (pin "6") (pinfunction "IN-_6") (pintype "input"))
      (node (ref "PD8") (pin "2") (pinfunction "K_2") (pintype "passive"))
      (node (ref "R8") (pin "1") (pinfunction "1_1") (pintype "passive"))
    )
    (net (code "50") (name "Net-(IC4B-OUT)") (class "Default")
      (node (ref "C8") (pin "2") (pinfunction "2_2") (pintype "passive"))
      (node (ref "IC4") (pin "7") (pinfunction "OUT_7") (pintype "output"))
      (node (ref "R16") (pin "1") (pinfunction "1_1") (pintype "passive"))
      (node (ref "R8") (pin "2") (pinfunction "2_2") (pintype "passive"))
    )
    (net (code "51") (name "Net-(IC7A-IN-)") (class "Default")
      (node (ref "C54") (pin "1") (pinfunction "1_1") (pintype "passive"))
      (node (ref "IC7") (pin "2") (pinfunction "IN-_2") (pintype "input"))
      (node (ref "PD14") (pin "2") (pinfunction "K_2") (pintype "passive"))
      (node (ref "R22") (pin "1") (pinfunction "1_1") (pintype "passive"))
    )
    (net (code "52") (name "Net-(IC7A-OUT)") (class "Default")
      (node (ref "C54") (pin "2") (pinfunction "2_2") (pintype "passive"))
      (node (ref "IC7") (pin "1") (pinfunction "OUT_1") (pintype "output"))
      (node (ref "R22") (pin "2") (pinfunction "2_2") (pintype "passive"))
      (node (ref "R30") (pin "1") (pinfunction "1_1") (pintype "passive"))
    )
    (net (code "53") (name "Net-(IC7B-IN-)") (class "Default")
      (node (ref "C53") (pin "1") (pinfunction "1_1") (pintype "passive"))
      (node (ref "IC7") (pin "6") (pinfunction "IN-_6") (pintype "input"))
      (node (ref "PD13") (pin "2") (pinfunction "K_2") (pintype "passive"))
      (node (ref "R21") (pin "1") (pinfunction "1_1") (pintype "passive"))
    )
    (net (code "54") (name "Net-(IC7B-OUT)") (class "Default")
      (node (ref "C53") (pin "2") (pinfunction "2_2") (pintype "passive"))
      (node (ref "IC7") (pin "7") (pinfunction "OUT_7") (pintype "output"))
      (node (ref "R21") (pin "2") (pinfunction "2_2") (pintype "passive"))
      (node (ref "R29") (pin "1") (pinfunction "1_1") (pintype "passive"))
    )
    (net (code "55") (name "Net-(IC8A-IN-)") (class "Default")
      (node (ref "C60") (pin "1") (pinfunction "1_1") (pintype "passive"))
      (node (ref "IC8") (pin "2") (pinfunction "IN-_2") (pintype "input"))
      (node (ref "PD16") (pin "2") (pinfunction "K_2") (pintype "passive"))
      (node (ref "R24") (pin "1") (pinfunction "1_1") (pintype "passive"))
    )
    (net (code "56") (name "Net-(IC8A-OUT)") (class "Default")
      (node (ref "C60") (pin "2") (pinfunction "2_2") (pintype "passive"))
      (node (ref "IC8") (pin "1") (pinfunction "OUT_1") (pintype "output"))
      (node (ref "R24") (pin "2") (pinfunction "2_2") (pintype "passive"))
      (node (ref "R32") (pin "1") (pinfunction "1_1") (pintype "passive"))
    )
    (net (code "57") (name "Net-(IC8B-IN-)") (class "Default")
      (node (ref "C59") (pin "1") (pinfunction "1_1") (pintype "passive"))
      (node (ref "IC8") (pin "6") (pinfunction "IN-_6") (pintype "input"))
      (node (ref "PD15") (pin "2") (pinfunction "K_2") (pintype "passive"))
      (node (ref "R23") (pin "1") (pinfunction "1_1") (pintype "passive"))
    )
    (net (code "58") (name "Net-(IC8B-OUT)") (class "Default")
      (node (ref "C59") (pin "2") (pinfunction "2_2") (pintype "passive"))
      (node (ref "IC8") (pin "7") (pinfunction "OUT_7") (pintype "output"))
      (node (ref "R23") (pin "2") (pinfunction "2_2") (pintype "passive"))
      (node (ref "R31") (pin "1") (pinfunction "1_1") (pintype "passive"))
    )
    (net (code "59") (name "Net-(IC11A-IN-)") (class "Default")
      (node (ref "C101") (pin "1") (pinfunction "1_1") (pintype "passive"))
      (node (ref "IC11") (pin "2") (pinfunction "IN-_2") (pintype "input"))
      (node (ref "PD21") (pin "2") (pinfunction "K_2") (pintype "passive"))
      (node (ref "R37") (pin "1") (pinfunction "1_1") (pintype "passive"))
    )
    (net (code "60") (name "Net-(IC11A-OUT)") (class "Default")
      (node (ref "C101") (pin "2") (pinfunction "2_2") (pintype "passive"))
      (node (ref "IC11") (pin "1") (pinfunction "OUT_1") (pintype "output"))
      (node (ref "R37") (pin "2") (pinfunction "2_2") (pintype "passive"))
      (node (ref "R45") (pin "1") (pinfunction "1_1") (pintype "passive"))
    )
    (net (code "61") (name "Net-(IC11B-IN-)") (class "Default")
      (node (ref "C102") (pin "1") (pinfunction "1_1") (pintype "passive"))
      (node (ref "IC11") (pin "6") (pinfunction "IN-_6") (pintype "input"))
      (node (ref "PD22") (pin "2") (pinfunction "K_2") (pintype "passive"))
      (node (ref "R38") (pin "1") (pinfunction "1_1") (pintype "passive"))
    )
    (net (code "62") (name "Net-(IC11B-OUT)") (class "Default")
      (node (ref "C102") (pin "2") (pinfunction "2_2") (pintype "passive"))
      (node (ref "IC11") (pin "7") (pinfunction "OUT_7") (pintype "output"))
      (node (ref "R38") (pin "2") (pinfunction "2_2") (pintype "passive"))
      (node (ref "R46") (pin "1") (pinfunction "1_1") (pintype "passive"))
    )
    (net (code "63") (name "Net-(IC12A-IN-)") (class "Default")
      (node (ref "C103") (pin "1") (pinfunction "1_1") (pintype "passive"))
      (node (ref "IC12") (pin "2") (pinfunction "IN-_2") (pintype "input"))
      (node (ref "PD23") (pin "2") (pinfunction "K_2") (pintype "passive"))
      (node (ref "R39") (pin "1") (pinfunction "1_1") (pintype "passive"))
    )
    (net (code "64") (name "Net-(IC12A-OUT)") (class "Default")
      (node (ref "C103") (pin "2") (pinfunction "2_2") (pintype "passive"))
      (node (ref "IC12") (pin "1") (pinfunction "OUT_1") (pintype "output"))
      (node (ref "R39") (pin "2") (pinfunction "2_2") (pintype "passive"))
      (node (ref "R47") (pin "1") (pinfunction "1_1") (pintype "passive"))
    )
    (net (code "65") (name "Net-(IC12B-IN-)") (class "Default")
      (node (ref "C104") (pin "1") (pinfunction "1_1") (pintype "passive"))
      (node (ref "IC12") (pin "6") (pinfunction "IN-_6") (pintype "input"))
      (node (ref "PD24") (pin "2") (pinfunction "K_2") (pintype "passive"))
      (node (ref "R40") (pin "1") (pinfunction "1_1") (pintype "passive"))
    )
    (net (code "66") (name "Net-(IC12B-OUT)") (class "Default")
      (node (ref "C104") (pin "2") (pinfunction "2_2") (pintype "passive"))
      (node (ref "IC12") (pin "7") (pinfunction "OUT_7") (pintype "output"))
      (node (ref "R40") (pin "2") (pinfunction "2_2") (pintype "passive"))
      (node (ref "R48") (pin "1") (pinfunction "1_1") (pintype "passive"))
    )
    (net (code "67") (name "Net-(IC15A-IN-)") (class "Default")
      (node (ref "C150") (pin "1") (pinfunction "1_1") (pintype "passive"))
      (node (ref "IC15") (pin "2") (pinfunction "IN-_2") (pintype "input"))
      (node (ref "PD30") (pin "2") (pinfunction "K_2") (pintype "passive"))
      (node (ref "R54") (pin "1") (pinfunction "1_1") (pintype "passive"))
    )
    (net (code "68") (name "Net-(IC15A-OUT)") (class "Default")
      (node (ref "C150") (pin "2") (pinfunction "2_2") (pintype "passive"))
      (node (ref "IC15") (pin "1") (pinfunction "OUT_1") (pintype "output"))
      (node (ref "R54") (pin "2") (pinfunction "2_2") (pintype "passive"))
      (node (ref "R62") (pin "1") (pinfunction "1_1") (pintype "passive"))
    )
    (net (code "69") (name "Net-(IC15B-IN-)") (class "Default")
      (node (ref "C149") (pin "1") (pinfunction "1_1") (pintype "passive"))
      (node (ref "IC15") (pin "6") (pinfunction "IN-_6") (pintype "input"))
      (node (ref "PD29") (pin "2") (pinfunction "K_2") (pintype "passive"))
      (node (ref "R53") (pin "1") (pinfunction "1_1") (pintype "passive"))
    )
    (net (code "70") (name "Net-(IC15B-OUT)") (class "Default")
      (node (ref "C149") (pin "2") (pinfunction "2_2") (pintype "passive"))
      (node (ref "IC15") (pin "7") (pinfunction "OUT_7") (pintype "output"))
      (node (ref "R53") (pin "2") (pinfunction "2_2") (pintype "passive"))
      (node (ref "R61") (pin "1") (pinfunction "1_1") (pintype "passive"))
    )
    (net (code "71") (name "Net-(IC16A-IN-)") (class "Default")
      (node (ref "C152") (pin "1") (pinfunction "1_1") (pintype "passive"))
      (node (ref "IC16") (pin "2") (pinfunction "IN-_2") (pintype "input"))
      (node (ref "PD32") (pin "2") (pinfunction "K_2") (pintype "passive"))
      (node (ref "R56") (pin "1") (pinfunction "1_1") (pintype "passive"))
    )
    (net (code "72") (name "Net-(IC16A-OUT)") (class "Default")
      (node (ref "C152") (pin "2") (pinfunction "2_2") (pintype "passive"))
      (node (ref "IC16") (pin "1") (pinfunction "OUT_1") (pintype "output"))
      (node (ref "R56") (pin "2") (pinfunction "2_2") (pintype "passive"))
      (node (ref "R64") (pin "1") (pinfunction "1_1") (pintype "passive"))
    )
    (net (code "73") (name "Net-(IC16B-IN-)") (class "Default")
      (node (ref "C151") (pin "1") (pinfunction "1_1") (pintype "passive"))
      (node (ref "IC16") (pin "6") (pinfunction "IN-_6") (pintype "input"))
      (node (ref "PD31") (pin "2") (pinfunction "K_2") (pintype "passive"))
      (node (ref "R55") (pin "1") (pinfunction "1_1") (pintype "passive"))
    )
    (net (code "74") (name "Net-(IC16B-OUT)") (class "Default")
      (node (ref "C151") (pin "2") (pinfunction "2_2") (pintype "passive"))
      (node (ref "IC16") (pin "7") (pinfunction "OUT_7") (pintype "output"))
      (node (ref "R55") (pin "2") (pinfunction "2_2") (pintype "passive"))
      (node (ref "R63") (pin "1") (pinfunction "1_1") (pintype "passive"))
    )
    (net (code "75") (name "VREF_PD") (class "Default")
      (node (ref "C125") (pin "2") (pinfunction "2_2") (pintype "passive"))
      (node (ref "C126") (pin "2") (pinfunction "2_2") (pintype "passive"))
      (node (ref "C127") (pin "2") (pinfunction "2_2") (pintype "passive"))
      (node (ref "C128") (pin "2") (pinfunction "2_2") (pintype "passive"))
      (node (ref "C185") (pin "2") (pinfunction "2_2") (pintype "passive"))
      (node (ref "C186") (pin "2") (pinfunction "2_2") (pintype "passive"))
      (node (ref "C189") (pin "2") (pinfunction "2_2") (pintype "passive"))
      (node (ref "C190") (pin "2") (pinfunction "2_2") (pintype "passive"))
      (node (ref "C29") (pin "2") (pinfunction "2_2") (pintype "passive"))
      (node (ref "C30") (pin "2") (pinfunction "2_2") (pintype "passive"))
      (node (ref "C31") (pin "2") (pinfunction "2_2") (pintype "passive"))
      (node (ref "C32") (pin "2") (pinfunction "2_2") (pintype "passive"))
      (node (ref "C75") (pin "2") (pinfunction "2_2") (pintype "passive"))
      (node (ref "C76") (pin "2") (pinfunction "2_2") (pintype "passive"))
      (node (ref "C79") (pin "2") (pinfunction "2_2") (pintype "passive"))
      (node (ref "C80") (pin "2") (pinfunction "2_2") (pintype "passive"))
      (node (ref "IC11") (pin "3") (pinfunction "IN+_3") (pintype "input"))
      (node (ref "IC11") (pin "5") (pinfunction "IN+_5") (pintype "input"))
      (node (ref "IC12") (pin "3") (pinfunction "IN+_3") (pintype "input"))
      (node (ref "IC12") (pin "5") (pinfunction "IN+_5") (pintype "input"))
      (node (ref "IC15") (pin "3") (pinfunction "IN+_3") (pintype "input"))
      (node (ref "IC15") (pin "5") (pinfunction "IN+_5") (pintype "input"))
      (node (ref "IC16") (pin "3") (pinfunction "IN+_3") (pintype "input"))
      (node (ref "IC16") (pin "5") (pinfunction "IN+_5") (pintype "input"))
      (node (ref "IC3") (pin "3") (pinfunction "IN+_3") (pintype "input"))
      (node (ref "IC3") (pin "5") (pinfunction "IN+_5") (pintype "input"))
      (node (ref "IC4") (pin "3") (pinfunction "IN+_3") (pintype "input"))
      (node (ref "IC4") (pin "5") (pinfunction "IN+_5") (pintype "input"))
      (node (ref "IC7") (pin "3") (pinfunction "IN+_3") (pintype "input"))
      (node (ref "IC7") (pin "5") (pinfunction "IN+_5") (pintype "input"))
      (node (ref "IC8") (pin "3") (pinfunction "IN+_3") (pintype "input"))
      (node (ref "IC8") (pin "5") (pinfunction "IN+_5") (pintype "input"))
    )
  )
)
